# FPGA_Decouple.net
KiCad netlist of a schematic drawn in Altium Designer
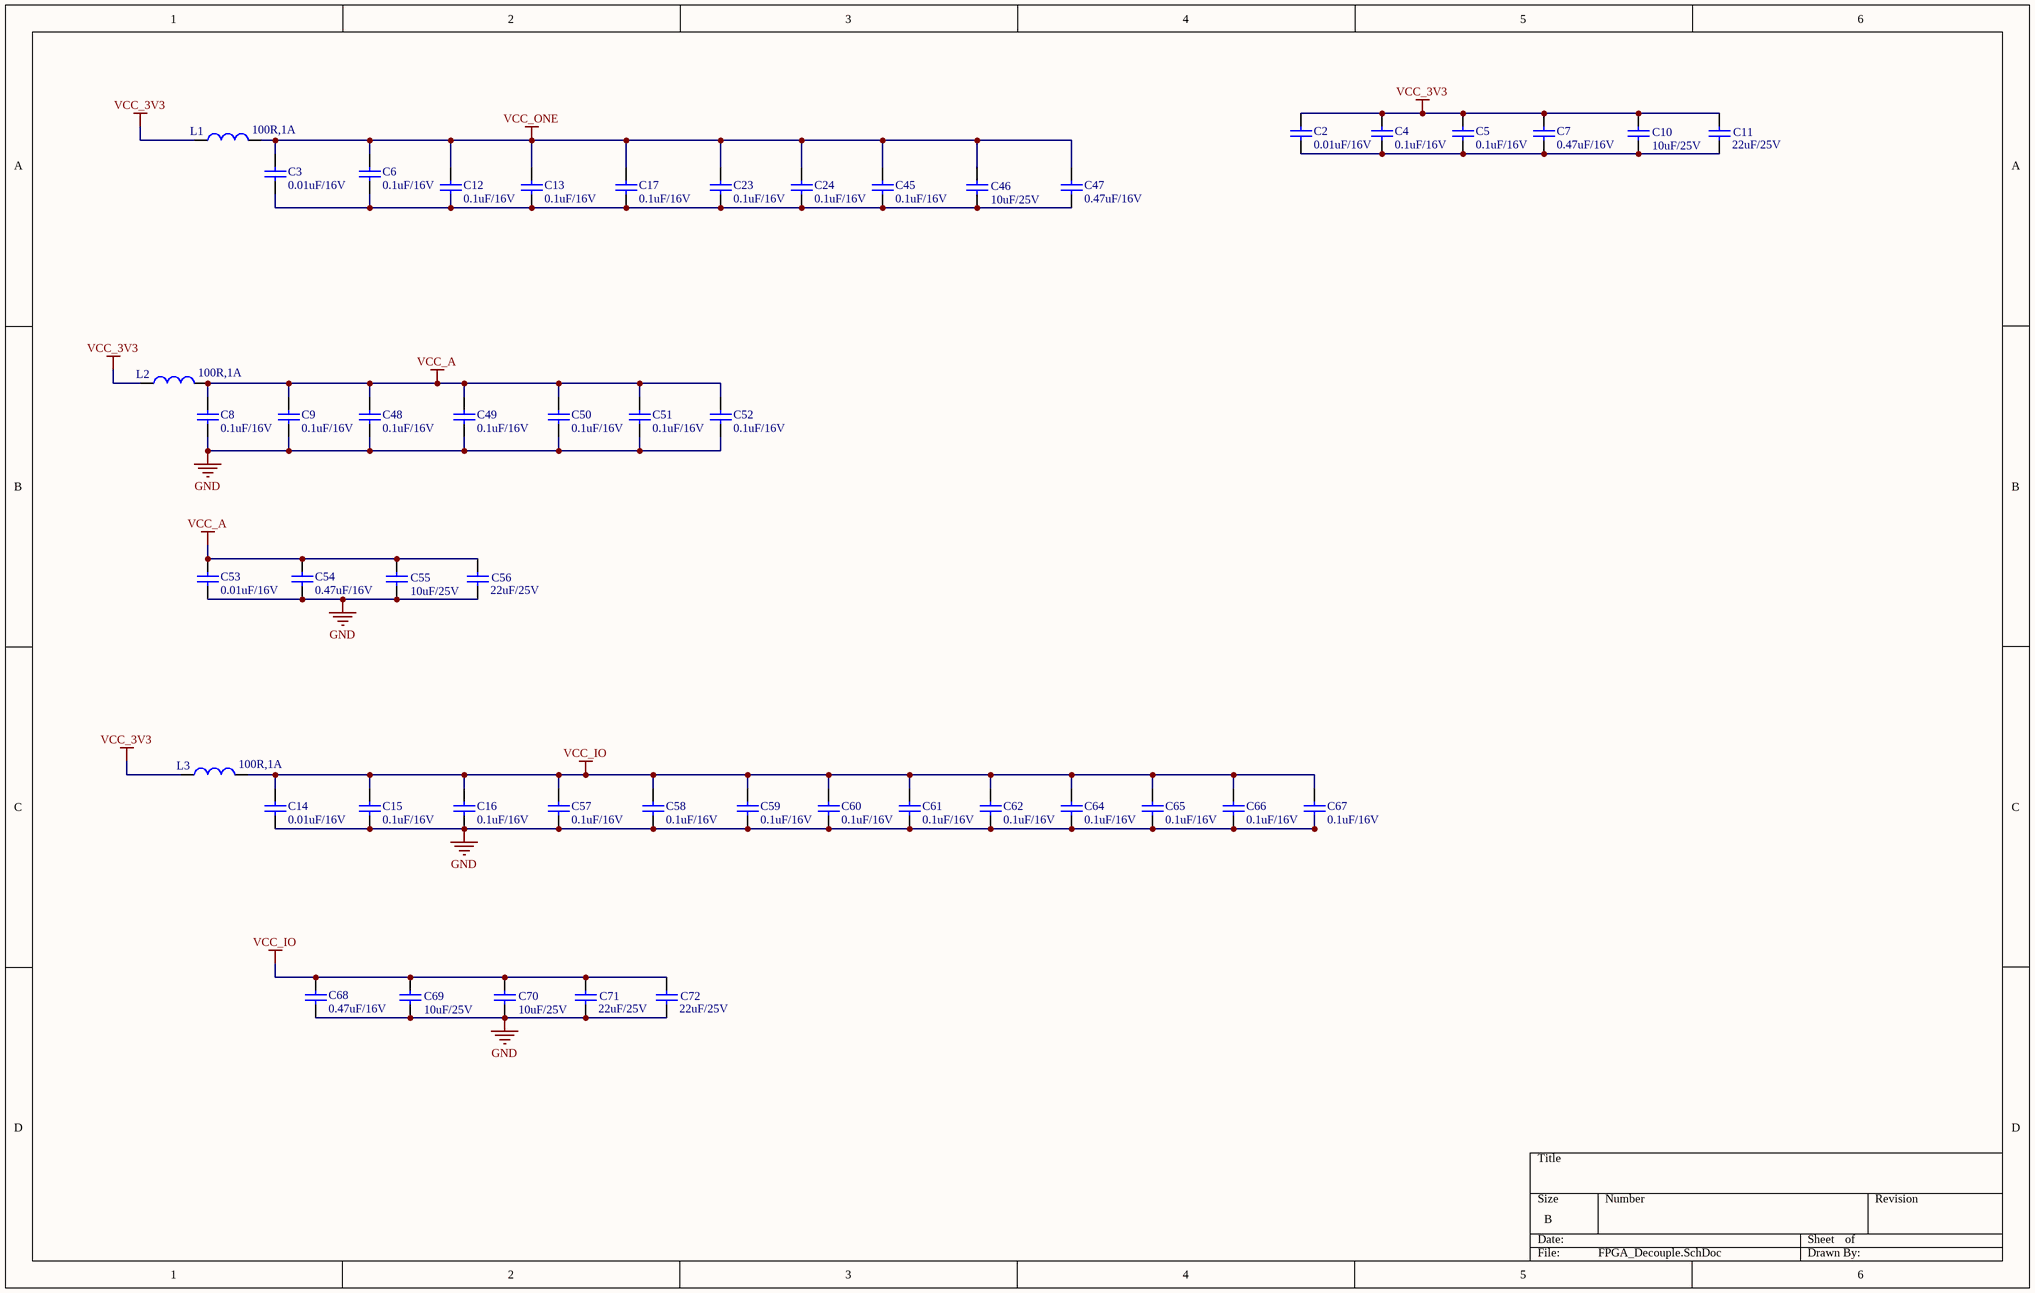
[diagram p0: FPGA_Decouple.SchDoc]

(export (version "E")
  (design (tool "Eeschema 10.0.6"))
  (components
    (comp (ref "C2")
      (value "0.01uF/16V")
      (footprint "0603C")
      (description "Multilayer Ceramic Capacitors MLCC - SMD/SMT 16V 0.01uF X7R 0603 10% AEC-Q200")
      (fields (field (name "MFR") "KEMET") (field (name "MFR PART NO") "C0603C103K4RECAUTO"))
      (libsource (lib "Miscellaneous Devices") (part "Cap"))
    )
    (comp (ref "C3")
      (value "0.01uF/16V")
      (footprint "0603C")
      (description "Multilayer Ceramic Capacitors MLCC - SMD/SMT 16V 0.01uF X7R 0603 10% AEC-Q200")
      (fields (field (name "MFR") "KEMET") (field (name "MFR PART NO") "C0603C103K4RECAUTO"))
      (libsource (lib "Miscellaneous Devices") (part "Cap"))
    )
    (comp (ref "C4")
      (value "0.1uF/16V")
      (footprint "0603C")
      (description "Multilayer Ceramic Capacitors MLCC - SMD/SMT 0603 16VDC 0.1uF 10% X7R AEC-Q200")
      (fields (field (name "MFR") "Taiyo Yuden") (field (name "MFR PART NO") "EMK107B7104KAHT"))
      (libsource (lib "Miscellaneous Devices") (part "Cap"))
    )
    (comp (ref "C5")
      (value "0.1uF/16V")
      (footprint "0603C")
      (description "Multilayer Ceramic Capacitors MLCC - SMD/SMT 0603 16VDC 0.1uF 10% X7R AEC-Q200")
      (fields (field (name "MFR") "Taiyo Yuden") (field (name "MFR PART NO") "EMK107B7104KAHT"))
      (libsource (lib "Miscellaneous Devices") (part "Cap"))
    )
    (comp (ref "C6")
      (value "0.1uF/16V")
      (footprint "0603C")
      (description "Multilayer Ceramic Capacitors MLCC - SMD/SMT 0603 16VDC 0.1uF 10% X7R AEC-Q200")
      (fields (field (name "MFR") "Taiyo Yuden") (field (name "MFR PART NO") "EMK107B7104KAHT"))
      (libsource (lib "Miscellaneous Devices") (part "Cap"))
    )
    (comp (ref "C7")
      (value "0.47uF/16V")
      (footprint "0603C")
      (description "Multilayer Ceramic Capacitors MLCC - SMD/SMT 16V 0.47uF 0603 X7R 5% AEC-Q200")
      (fields (field (name "MFR") "KEMET") (field (name "MFR PART NO") "C0603C474J4RACAUTO"))
      (libsource (lib "Miscellaneous Devices") (part "Cap"))
    )
    (comp (ref "C8")
      (value "0.1uF/16V")
      (footprint "0603C")
      (description "Multilayer Ceramic Capacitors MLCC - SMD/SMT 0603 16VDC 0.1uF 10% X7R AEC-Q200")
      (fields (field (name "MFR") "Taiyo Yuden") (field (name "MFR PART NO") "EMK107B7104KAHT"))
      (libsource (lib "Miscellaneous Devices") (part "Cap"))
    )
    (comp (ref "C9")
      (value "0.1uF/16V")
      (footprint "0603C")
      (description "Multilayer Ceramic Capacitors MLCC - SMD/SMT 0603 16VDC 0.1uF 10% X7R AEC-Q200")
      (fields (field (name "MFR") "Taiyo Yuden") (field (name "MFR PART NO") "EMK107B7104KAHT"))
      (libsource (lib "Miscellaneous Devices") (part "Cap"))
    )
    (comp (ref "C10")
      (value "10uF/25V")
      (footprint "0805C")
      (description "Multilayer Ceramic Capacitors MLCC - SMD/SMT 0805 25VDC 10uF 20% X5R")
      (fields (field (name "MFR") "Taiyo Yuden") (field (name "MFR PART NO") "TMK212BBJ106MG-T"))
      (libsource (lib "Miscellaneous Devices") (part "Cap"))
    )
    (comp (ref "C11")
      (value "22uF/25V")
      (footprint "1210C")
      (description "Multilayer Ceramic Capacitors MLCC - SMD/SMT 1210 25VDC 22uF 20% X7R AEC-Q200")
      (fields (field (name "MFR") "Taiyo Yuden") (field (name "MFR PART NO") "TMK325B7226MMHP"))
      (libsource (lib "Miscellaneous Devices") (part "Cap"))
    )
    (comp (ref "C12")
      (value "0.1uF/16V")
      (footprint "0603C")
      (description "Multilayer Ceramic Capacitors MLCC - SMD/SMT 0603 16VDC 0.1uF 10% X7R AEC-Q200")
      (fields (field (name "MFR") "Taiyo Yuden") (field (name "MFR PART NO") "EMK107B7104KAHT"))
      (libsource (lib "Miscellaneous Devices") (part "Cap"))
    )
    (comp (ref "C13")
      (value "0.1uF/16V")
      (footprint "0603C")
      (description "Multilayer Ceramic Capacitors MLCC - SMD/SMT 0603 16VDC 0.1uF 10% X7R AEC-Q200")
      (fields (field (name "MFR") "Taiyo Yuden") (field (name "MFR PART NO") "EMK107B7104KAHT"))
      (libsource (lib "Miscellaneous Devices") (part "Cap"))
    )
    (comp (ref "C14")
      (value "0.01uF/16V")
      (footprint "0603C")
      (description "Multilayer Ceramic Capacitors MLCC - SMD/SMT 16V 0.01uF X7R 0603 10% AEC-Q200")
      (fields (field (name "MFR") "KEMET") (field (name "MFR PART NO") "C0603C103K4RECAUTO"))
      (libsource (lib "Miscellaneous Devices") (part "Cap"))
    )
    (comp (ref "C15")
      (value "0.1uF/16V")
      (footprint "0603C")
      (description "Multilayer Ceramic Capacitors MLCC - SMD/SMT 0603 16VDC 0.1uF 10% X7R AEC-Q200")
      (fields (field (name "MFR") "Taiyo Yuden") (field (name "MFR PART NO") "EMK107B7104KAHT"))
      (libsource (lib "Miscellaneous Devices") (part "Cap"))
    )
    (comp (ref "C16")
      (value "0.1uF/16V")
      (footprint "0603C")
      (description "Multilayer Ceramic Capacitors MLCC - SMD/SMT 0603 16VDC 0.1uF 10% X7R AEC-Q200")
      (fields (field (name "MFR") "Taiyo Yuden") (field (name "MFR PART NO") "EMK107B7104KAHT"))
      (libsource (lib "Miscellaneous Devices") (part "Cap"))
    )
    (comp (ref "C17")
      (value "0.1uF/16V")
      (footprint "0603C")
      (description "Multilayer Ceramic Capacitors MLCC - SMD/SMT 0603 16VDC 0.1uF 10% X7R AEC-Q200")
      (fields (field (name "MFR") "Taiyo Yuden") (field (name "MFR PART NO") "EMK107B7104KAHT"))
      (libsource (lib "Miscellaneous Devices") (part "Cap"))
    )
    (comp (ref "C23")
      (value "0.1uF/16V")
      (footprint "0603C")
      (description "Multilayer Ceramic Capacitors MLCC - SMD/SMT 0603 16VDC 0.1uF 10% X7R AEC-Q200")
      (fields (field (name "MFR") "Taiyo Yuden") (field (name "MFR PART NO") "EMK107B7104KAHT"))
      (libsource (lib "Miscellaneous Devices") (part "Cap"))
    )
    (comp (ref "C24")
      (value "0.1uF/16V")
      (footprint "0603C")
      (description "Multilayer Ceramic Capacitors MLCC - SMD/SMT 0603 16VDC 0.1uF 10% X7R AEC-Q200")
      (fields (field (name "MFR") "Taiyo Yuden") (field (name "MFR PART NO") "EMK107B7104KAHT"))
      (libsource (lib "Miscellaneous Devices") (part "Cap"))
    )
    (comp (ref "C45")
      (value "0.1uF/16V")
      (footprint "0603C")
      (description "Multilayer Ceramic Capacitors MLCC - SMD/SMT 0603 16VDC 0.1uF 10% X7R AEC-Q200")
      (fields (field (name "MFR") "Taiyo Yuden") (field (name "MFR PART NO") "EMK107B7104KAHT"))
      (libsource (lib "Miscellaneous Devices") (part "Cap"))
    )
    (comp (ref "C46")
      (value "10uF/25V")
      (footprint "0805C")
      (description "Multilayer Ceramic Capacitors MLCC - SMD/SMT 0805 25VDC 10uF 20% X5R")
      (fields (field (name "MFR") "Taiyo Yuden") (field (name "MFR PART NO") "TMK212BBJ106MG-T"))
      (libsource (lib "Miscellaneous Devices") (part "Cap"))
    )
    (comp (ref "C47")
      (value "0.47uF/16V")
      (footprint "0603C")
      (description "Multilayer Ceramic Capacitors MLCC - SMD/SMT 16V 0.47uF 0603 X7R 5% AEC-Q200")
      (fields (field (name "MFR") "KEMET") (field (name "MFR PART NO") "C0603C474J4RACAUTO"))
      (libsource (lib "Miscellaneous Devices") (part "Cap"))
    )
    (comp (ref "C48")
      (value "0.1uF/16V")
      (footprint "0603C")
      (description "Multilayer Ceramic Capacitors MLCC - SMD/SMT 0603 16VDC 0.1uF 10% X7R AEC-Q200")
      (fields (field (name "MFR") "Taiyo Yuden") (field (name "MFR PART NO") "EMK107B7104KAHT"))
      (libsource (lib "Miscellaneous Devices") (part "Cap"))
    )
    (comp (ref "C49")
      (value "0.1uF/16V")
      (footprint "0603C")
      (description "Multilayer Ceramic Capacitors MLCC - SMD/SMT 0603 16VDC 0.1uF 10% X7R AEC-Q200")
      (fields (field (name "MFR") "Taiyo Yuden") (field (name "MFR PART NO") "EMK107B7104KAHT"))
      (libsource (lib "Miscellaneous Devices") (part "Cap"))
    )
    (comp (ref "C50")
      (value "0.1uF/16V")
      (footprint "0603C")
      (description "Multilayer Ceramic Capacitors MLCC - SMD/SMT 0603 16VDC 0.1uF 10% X7R AEC-Q200")
      (fields (field (name "MFR") "Taiyo Yuden") (field (name "MFR PART NO") "EMK107B7104KAHT"))
      (libsource (lib "Miscellaneous Devices") (part "Cap"))
    )
    (comp (ref "C51")
      (value "0.1uF/16V")
      (footprint "0603C")
      (description "Multilayer Ceramic Capacitors MLCC - SMD/SMT 0603 16VDC 0.1uF 10% X7R AEC-Q200")
      (fields (field (name "MFR") "Taiyo Yuden") (field (name "MFR PART NO") "EMK107B7104KAHT"))
      (libsource (lib "Miscellaneous Devices") (part "Cap"))
    )
    (comp (ref "C52")
      (value "0.1uF/16V")
      (footprint "0603C")
      (description "Multilayer Ceramic Capacitors MLCC - SMD/SMT 0603 16VDC 0.1uF 10% X7R AEC-Q200")
      (fields (field (name "MFR") "Taiyo Yuden") (field (name "MFR PART NO") "EMK107B7104KAHT"))
      (libsource (lib "Miscellaneous Devices") (part "Cap"))
    )
    (comp (ref "C53")
      (value "0.01uF/16V")
      (footprint "0603C")
      (description "Multilayer Ceramic Capacitors MLCC - SMD/SMT 16V 0.01uF X7R 0603 10% AEC-Q200")
      (fields (field (name "MFR") "KEMET") (field (name "MFR PART NO") "C0603C103K4RECAUTO"))
      (libsource (lib "Miscellaneous Devices") (part "Cap"))
    )
    (comp (ref "C54")
      (value "0.47uF/16V")
      (footprint "0603C")
      (description "Multilayer Ceramic Capacitors MLCC - SMD/SMT 16V 0.47uF 0603 X7R 5% AEC-Q200")
      (fields (field (name "MFR") "KEMET") (field (name "MFR PART NO") "C0603C474J4RACAUTO"))
      (libsource (lib "Miscellaneous Devices") (part "Cap"))
    )
    (comp (ref "C55")
      (value "10uF/25V")
      (footprint "0805C")
      (description "Multilayer Ceramic Capacitors MLCC - SMD/SMT 0805 25VDC 10uF 20% X5R")
      (fields (field (name "MFR") "Taiyo Yuden") (field (name "MFR PART NO") "TMK212BBJ106MG-T"))
      (libsource (lib "Miscellaneous Devices") (part "Cap"))
    )
    (comp (ref "C56")
      (value "22uF/25V")
      (footprint "1210C")
      (description "Multilayer Ceramic Capacitors MLCC - SMD/SMT 1210 25VDC 22uF 20% X7R AEC-Q200")
      (fields (field (name "MFR") "Taiyo Yuden") (field (name "MFR PART NO") "TMK325B7226MMHP"))
      (libsource (lib "Miscellaneous Devices") (part "Cap"))
    )
    (comp (ref "C57")
      (value "0.1uF/16V")
      (footprint "0603C")
      (description "Multilayer Ceramic Capacitors MLCC - SMD/SMT 0603 16VDC 0.1uF 10% X7R AEC-Q200")
      (fields (field (name "MFR") "Taiyo Yuden") (field (name "MFR PART NO") "EMK107B7104KAHT"))
      (libsource (lib "Miscellaneous Devices") (part "Cap"))
    )
    (comp (ref "C58")
      (value "0.1uF/16V")
      (footprint "0603C")
      (description "Multilayer Ceramic Capacitors MLCC - SMD/SMT 0603 16VDC 0.1uF 10% X7R AEC-Q200")
      (fields (field (name "MFR") "Taiyo Yuden") (field (name "MFR PART NO") "EMK107B7104KAHT"))
      (libsource (lib "Miscellaneous Devices") (part "Cap"))
    )
    (comp (ref "C59")
      (value "0.1uF/16V")
      (footprint "0603C")
      (description "Multilayer Ceramic Capacitors MLCC - SMD/SMT 0603 16VDC 0.1uF 10% X7R AEC-Q200")
      (fields (field (name "MFR") "Taiyo Yuden") (field (name "MFR PART NO") "EMK107B7104KAHT"))
      (libsource (lib "Miscellaneous Devices") (part "Cap"))
    )
    (comp (ref "C60")
      (value "0.1uF/16V")
      (footprint "0603C")
      (description "Multilayer Ceramic Capacitors MLCC - SMD/SMT 0603 16VDC 0.1uF 10% X7R AEC-Q200")
      (fields (field (name "MFR") "Taiyo Yuden") (field (name "MFR PART NO") "EMK107B7104KAHT"))
      (libsource (lib "Miscellaneous Devices") (part "Cap"))
    )
    (comp (ref "C61")
      (value "0.1uF/16V")
      (footprint "0603C")
      (description "Multilayer Ceramic Capacitors MLCC - SMD/SMT 0603 16VDC 0.1uF 10% X7R AEC-Q200")
      (fields (field (name "MFR") "Taiyo Yuden") (field (name "MFR PART NO") "EMK107B7104KAHT"))
      (libsource (lib "Miscellaneous Devices") (part "Cap"))
    )
    (comp (ref "C62")
      (value "0.1uF/16V")
      (footprint "0603C")
      (description "Multilayer Ceramic Capacitors MLCC - SMD/SMT 0603 16VDC 0.1uF 10% X7R AEC-Q200")
      (fields (field (name "MFR") "Taiyo Yuden") (field (name "MFR PART NO") "EMK107B7104KAHT"))
      (libsource (lib "Miscellaneous Devices") (part "Cap"))
    )
    (comp (ref "C64")
      (value "0.1uF/16V")
      (footprint "0603C")
      (description "Multilayer Ceramic Capacitors MLCC - SMD/SMT 0603 16VDC 0.1uF 10% X7R AEC-Q200")
      (fields (field (name "MFR") "Taiyo Yuden") (field (name "MFR PART NO") "EMK107B7104KAHT"))
      (libsource (lib "Miscellaneous Devices") (part "Cap"))
    )
    (comp (ref "C65")
      (value "0.1uF/16V")
      (footprint "0603C")
      (description "Multilayer Ceramic Capacitors MLCC - SMD/SMT 0603 16VDC 0.1uF 10% X7R AEC-Q200")
      (fields (field (name "MFR") "Taiyo Yuden") (field (name "MFR PART NO") "EMK107B7104KAHT"))
      (libsource (lib "Miscellaneous Devices") (part "Cap"))
    )
    (comp (ref "C66")
      (value "0.1uF/16V")
      (footprint "0603C")
      (description "Multilayer Ceramic Capacitors MLCC - SMD/SMT 0603 16VDC 0.1uF 10% X7R AEC-Q200")
      (fields (field (name "MFR") "Taiyo Yuden") (field (name "MFR PART NO") "EMK107B7104KAHT"))
      (libsource (lib "Miscellaneous Devices") (part "Cap"))
    )
    (comp (ref "C67")
      (value "0.1uF/16V")
      (footprint "0603C")
      (description "Multilayer Ceramic Capacitors MLCC - SMD/SMT 0603 16VDC 0.1uF 10% X7R AEC-Q200")
      (fields (field (name "MFR") "Taiyo Yuden") (field (name "MFR PART NO") "EMK107B7104KAHT"))
      (libsource (lib "Miscellaneous Devices") (part "Cap"))
    )
    (comp (ref "C68")
      (value "0.47uF/16V")
      (footprint "0603C")
      (description "Multilayer Ceramic Capacitors MLCC - SMD/SMT 16V 0.47uF 0603 X7R 5% AEC-Q200")
      (fields (field (name "MFR") "KEMET") (field (name "MFR PART NO") "C0603C474J4RACAUTO"))
      (libsource (lib "Miscellaneous Devices") (part "Cap"))
    )
    (comp (ref "C69")
      (value "10uF/25V")
      (footprint "0805C")
      (description "Multilayer Ceramic Capacitors MLCC - SMD/SMT 0805 25VDC 10uF 20% X5R")
      (fields (field (name "MFR") "Taiyo Yuden") (field (name "MFR PART NO") "TMK212BBJ106MG-T"))
      (libsource (lib "Miscellaneous Devices") (part "Cap"))
    )
    (comp (ref "C70")
      (value "10uF/25V")
      (footprint "0805C")
      (description "Multilayer Ceramic Capacitors MLCC - SMD/SMT 0805 25VDC 10uF 20% X5R")
      (fields (field (name "MFR") "Taiyo Yuden") (field (name "MFR PART NO") "TMK212BBJ106MG-T"))
      (libsource (lib "Miscellaneous Devices") (part "Cap"))
    )
    (comp (ref "C71")
      (value "22uF/25V")
      (footprint "1210C")
      (description "Multilayer Ceramic Capacitors MLCC - SMD/SMT 1210 25VDC 22uF 20% X7R AEC-Q200")
      (fields (field (name "MFR") "Taiyo Yuden") (field (name "MFR PART NO") "TMK325B7226MMHP"))
      (libsource (lib "Miscellaneous Devices") (part "Cap"))
    )
    (comp (ref "C72")
      (value "22uF/25V")
      (footprint "1210C")
      (description "Multilayer Ceramic Capacitors MLCC - SMD/SMT 1210 25VDC 22uF 20% X7R AEC-Q200")
      (fields (field (name "MFR") "Taiyo Yuden") (field (name "MFR PART NO") "TMK325B7226MMHP"))
      (libsource (lib "Miscellaneous Devices") (part "Cap"))
    )
    (comp (ref "L1")
      (value "100R,1A")
      (footprint "0603L")
      (description "Ferrite Beads 100ohms 1A 60mOhms 0603 Ferrite Chip")
      (fields (field (name "MFR") "TDK") (field (name "MFR PART NO") "MPZ1608D101BTA00"))
      (libsource (lib "de20") (part "0805_IND"))
    )
    (comp (ref "L2")
      (value "100R,1A")
      (footprint "0603L")
      (description "Ferrite Beads 100ohms 1A 60mOhms 0603 Ferrite Chip")
      (fields (field (name "MFR") "TDK") (field (name "MFR PART NO") "MPZ1608D101BTA00"))
      (libsource (lib "de20") (part "0805_IND"))
    )
    (comp (ref "L3")
      (value "100R,1A")
      (footprint "0603L")
      (description "Ferrite Beads 100ohms 1A 60mOhms 0603 Ferrite Chip")
      (fields (field (name "MFR") "TDK") (field (name "MFR PART NO") "MPZ1608D101BTA00"))
      (libsource (lib "de20") (part "0805_IND"))
    )
  )
  (nets
    (net (code "1") (name "GND") (class "Default")
      (node (ref "C14") (pin "2") (pinfunction "2_2") (pintype "passive"))
      (node (ref "C15") (pin "2") (pinfunction "2_2") (pintype "passive"))
      (node (ref "C16") (pin "2") (pinfunction "2_2") (pintype "passive"))
      (node (ref "C48") (pin "2") (pinfunction "2_2") (pintype "passive"))
      (node (ref "C49") (pin "2") (pinfunction "2_2") (pintype "passive"))
      (node (ref "C50") (pin "2") (pinfunction "2_2") (pintype "passive"))
      (node (ref "C51") (pin "2") (pinfunction "2_2") (pintype "passive"))
      (node (ref "C52") (pin "2") (pinfunction "2_2") (pintype "passive"))
      (node (ref "C53") (pin "2") (pinfunction "2_2") (pintype "passive"))
      (node (ref "C54") (pin "2") (pinfunction "2_2") (pintype "passive"))
      (node (ref "C55") (pin "1") (pinfunction "1_1") (pintype "passive"))
      (node (ref "C56") (pin "1") (pinfunction "1_1") (pintype "passive"))
      (node (ref "C57") (pin "2") (pinfunction "2_2") (pintype "passive"))
      (node (ref "C58") (pin "2") (pinfunction "2_2") (pintype "passive"))
      (node (ref "C59") (pin "2") (pinfunction "2_2") (pintype "passive"))
      (node (ref "C60") (pin "2") (pinfunction "2_2") (pintype "passive"))
      (node (ref "C61") (pin "2") (pinfunction "2_2") (pintype "passive"))
      (node (ref "C62") (pin "2") (pinfunction "2_2") (pintype "passive"))
      (node (ref "C64") (pin "2") (pinfunction "2_2") (pintype "passive"))
      (node (ref "C65") (pin "2") (pinfunction "2_2") (pintype "passive"))
      (node (ref "C66") (pin "2") (pinfunction "2_2") (pintype "passive"))
      (node (ref "C67") (pin "2") (pinfunction "2_2") (pintype "passive"))
      (node (ref "C68") (pin "2") (pinfunction "2_2") (pintype "passive"))
      (node (ref "C69") (pin "1") (pinfunction "1_1") (pintype "passive"))
      (node (ref "C70") (pin "1") (pinfunction "1_1") (pintype "passive"))
      (node (ref "C71") (pin "1") (pinfunction "1_1") (pintype "passive"))
      (node (ref "C72") (pin "1") (pinfunction "1_1") (pintype "passive"))
      (node (ref "C8") (pin "2") (pinfunction "2_2") (pintype "passive"))
      (node (ref "C9") (pin "2") (pinfunction "2_2") (pintype "passive"))
    )
    (net (code "2") (name "Net-(C10-Pad1)") (class "Default")
      (node (ref "C10") (pin "1") (pinfunction "1_1") (pintype "passive"))
      (node (ref "C11") (pin "1") (pinfunction "1_1") (pintype "passive"))
      (node (ref "C2") (pin "2") (pinfunction "2_2") (pintype "passive"))
      (node (ref "C4") (pin "2") (pinfunction "2_2") (pintype "passive"))
      (node (ref "C5") (pin "2") (pinfunction "2_2") (pintype "passive"))
      (node (ref "C7") (pin "2") (pinfunction "2_2") (pintype "passive"))
    )
    (net (code "3") (name "Net-(C12-Pad2)") (class "Default")
      (node (ref "C12") (pin "2") (pinfunction "2_2") (pintype "passive"))
      (node (ref "C13") (pin "2") (pinfunction "2_2") (pintype "passive"))
      (node (ref "C17") (pin "2") (pinfunction "2_2") (pintype "passive"))
      (node (ref "C23") (pin "2") (pinfunction "2_2") (pintype "passive"))
      (node (ref "C24") (pin "2") (pinfunction "2_2") (pintype "passive"))
      (node (ref "C3") (pin "2") (pinfunction "2_2") (pintype "passive"))
      (node (ref "C45") (pin "2") (pinfunction "2_2") (pintype "passive"))
      (node (ref "C46") (pin "1") (pinfunction "1_1") (pintype "passive"))
      (node (ref "C47") (pin "2") (pinfunction "2_2") (pintype "passive"))
      (node (ref "C6") (pin "2") (pinfunction "2_2") (pintype "passive"))
    )
    (net (code "4") (name "VCC_3V3") (class "Default")
      (node (ref "C10") (pin "2") (pinfunction "2_2") (pintype "passive"))
      (node (ref "C11") (pin "2") (pinfunction "2_2") (pintype "passive"))
      (node (ref "C2") (pin "1") (pinfunction "1_1") (pintype "passive"))
      (node (ref "C4") (pin "1") (pinfunction "1_1") (pintype "passive"))
      (node (ref "C5") (pin "1") (pinfunction "1_1") (pintype "passive"))
      (node (ref "C7") (pin "1") (pinfunction "1_1") (pintype "passive"))
      (node (ref "L1") (pin "1") (pinfunction "1_1") (pintype "passive"))
      (node (ref "L2") (pin "1") (pinfunction "1_1") (pintype "passive"))
      (node (ref "L3") (pin "1") (pinfunction "1_1") (pintype "passive"))
    )
    (net (code "5") (name "VCC_A") (class "Default")
      (node (ref "C48") (pin "1") (pinfunction "1_1") (pintype "passive"))
      (node (ref "C49") (pin "1") (pinfunction "1_1") (pintype "passive"))
      (node (ref "C50") (pin "1") (pinfunction "1_1") (pintype "passive"))
      (node (ref "C51") (pin "1") (pinfunction "1_1") (pintype "passive"))
      (node (ref "C52") (pin "1") (pinfunction "1_1") (pintype "passive"))
      (node (ref "C53") (pin "1") (pinfunction "1_1") (pintype "passive"))
      (node (ref "C54") (pin "1") (pinfunction "1_1") (pintype "passive"))
      (node (ref "C55") (pin "2") (pinfunction "2_2") (pintype "passive"))
      (node (ref "C56") (pin "2") (pinfunction "2_2") (pintype "passive"))
      (node (ref "C8") (pin "1") (pinfunction "1_1") (pintype "passive"))
      (node (ref "C9") (pin "1") (pinfunction "1_1") (pintype "passive"))
      (node (ref "L2") (pin "2") (pinfunction "2_2") (pintype "passive"))
    )
    (net (code "6") (name "VCC_IO") (class "Default")
      (node (ref "C14") (pin "1") (pinfunction "1_1") (pintype "passive"))
      (node (ref "C15") (pin "1") (pinfunction "1_1") (pintype "passive"))
      (node (ref "C16") (pin "1") (pinfunction "1_1") (pintype "passive"))
      (node (ref "C57") (pin "1") (pinfunction "1_1") (pintype "passive"))
      (node (ref "C58") (pin "1") (pinfunction "1_1") (pintype "passive"))
      (node (ref "C59") (pin "1") (pinfunction "1_1") (pintype "passive"))
      (node (ref "C60") (pin "1") (pinfunction "1_1") (pintype "passive"))
      (node (ref "C61") (pin "1") (pinfunction "1_1") (pintype "passive"))
      (node (ref "C62") (pin "1") (pinfunction "1_1") (pintype "passive"))
      (node (ref "C64") (pin "1") (pinfunction "1_1") (pintype "passive"))
      (node (ref "C65") (pin "1") (pinfunction "1_1") (pintype "passive"))
      (node (ref "C66") (pin "1") (pinfunction "1_1") (pintype "passive"))
      (node (ref "C67") (pin "1") (pinfunction "1_1") (pintype "passive"))
      (node (ref "C68") (pin "1") (pinfunction "1_1") (pintype "passive"))
      (node (ref "C69") (pin "2") (pinfunction "2_2") (pintype "passive"))
      (node (ref "C70") (pin "2") (pinfunction "2_2") (pintype "passive"))
      (node (ref "C71") (pin "2") (pinfunction "2_2") (pintype "passive"))
      (node (ref "C72") (pin "2") (pinfunction "2_2") (pintype "passive"))
      (node (ref "L3") (pin "2") (pinfunction "2_2") (pintype "passive"))
    )
    (net (code "7") (name "VCC_ONE") (class "Default")
      (node (ref "C12") (pin "1") (pinfunction "1_1") (pintype "passive"))
      (node (ref "C13") (pin "1") (pinfunction "1_1") (pintype "passive"))
      (node (ref "C17") (pin "1") (pinfunction "1_1") (pintype "passive"))
      (node (ref "C23") (pin "1") (pinfunction "1_1") (pintype "passive"))
      (node (ref "C24") (pin "1") (pinfunction "1_1") (pintype "passive"))
      (node (ref "C3") (pin "1") (pinfunction "1_1") (pintype "passive"))
      (node (ref "C45") (pin "1") (pinfunction "1_1") (pintype "passive"))
      (node (ref "C46") (pin "2") (pinfunction "2_2") (pintype "passive"))
      (node (ref "C47") (pin "1") (pinfunction "1_1") (pintype "passive"))
      (node (ref "C6") (pin "1") (pinfunction "1_1") (pintype "passive"))
      (node (ref "L1") (pin "2") (pinfunction "2_2") (pintype "passive"))
    )
  )
)
